# FPGA_ADC3.net
KiCad netlist of a schematic drawn in Altium Designer
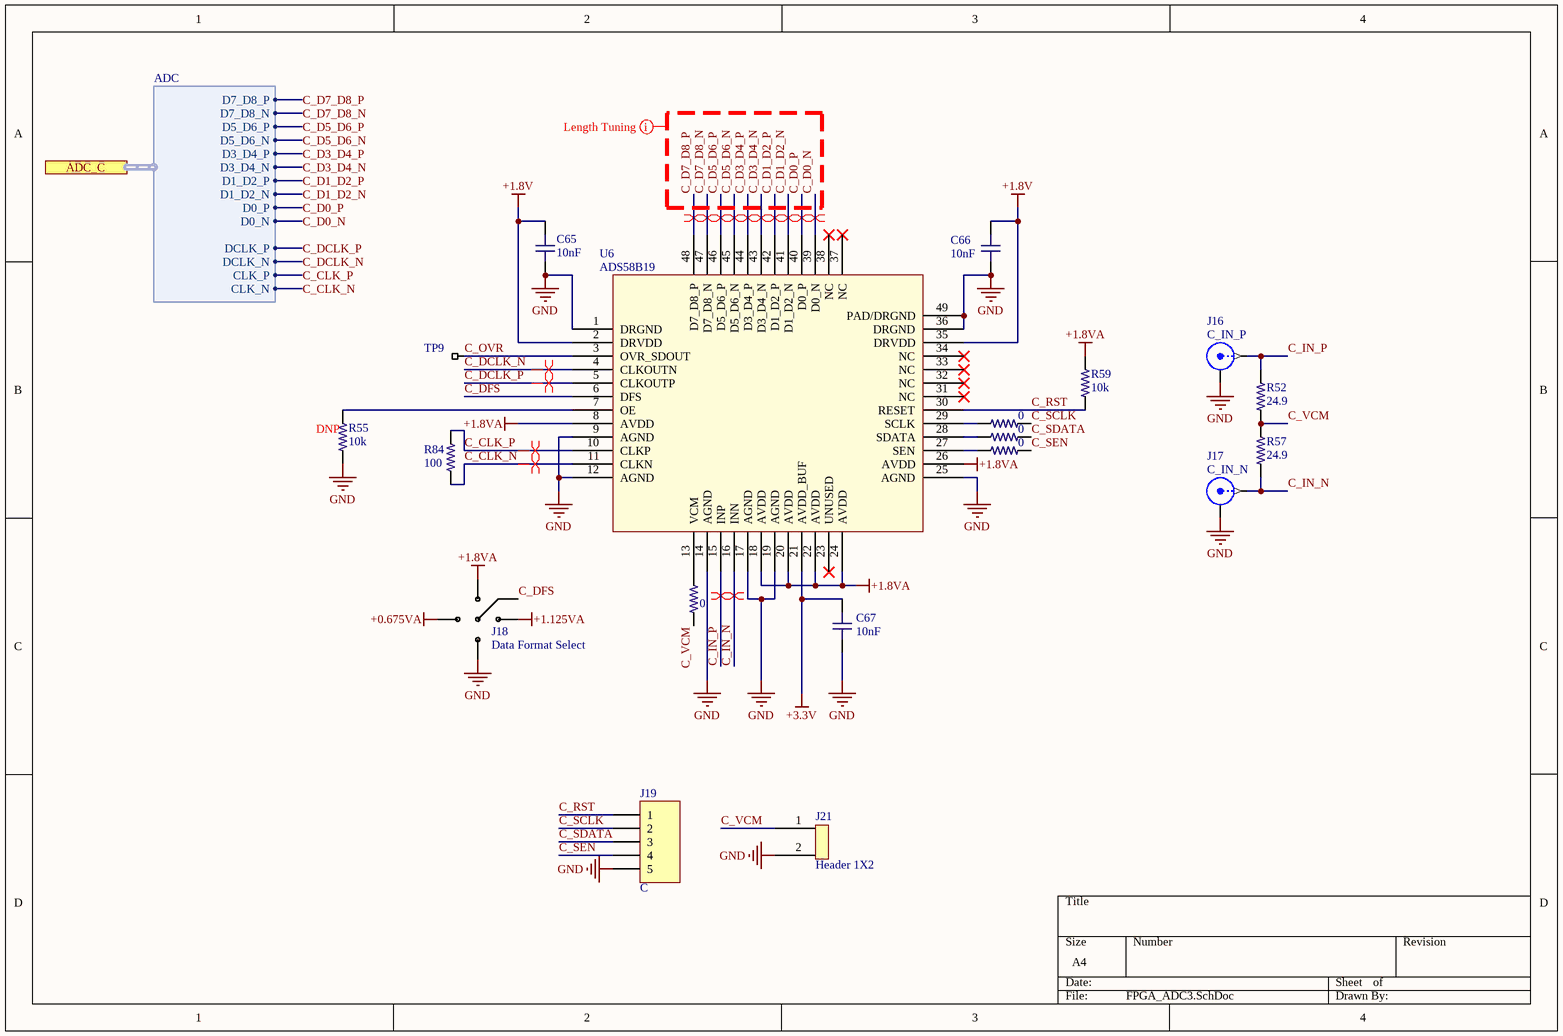
[diagram p0: FPGA_ADC3.SchDoc]

(export (version "E")
  (design (tool "Eeschema 10.0.6"))
  (components
    (comp (ref "C65")
      (value "10nF")
      (footprint "C0603-HIGH-DENSITY")
      (description "CAP CER 10000PF 50V X7R 0603")
      (fields (field (name "Comment") "C0603 10nF 50V X7R"))
      (libsource (lib "Capacitors") (part "C0603 10nF 50V X7R"))
    )
    (comp (ref "C66")
      (value "10nF")
      (footprint "C0603-HIGH-DENSITY")
      (description "CAP CER 10000PF 50V X7R 0603")
      (fields (field (name "Comment") "C0603 10nF 50V X7R"))
      (libsource (lib "Capacitors") (part "C0603 10nF 50V X7R"))
    )
    (comp (ref "C67")
      (value "10nF")
      (footprint "C0603-HIGH-DENSITY")
      (description "CAP CER 10000PF 50V X7R 0603")
      (fields (field (name "Comment") "C0603 10nF 50V X7R"))
      (libsource (lib "Capacitors") (part "C0603 10nF 50V X7R"))
    )
    (comp (ref "J16")
      (value "C_IN_P")
      (footprint "SMA Edge Launch (Horizontal)")
      (description "SMA Connector")
      (libsource (lib "Connectors") (part "SMA"))
    )
    (comp (ref "J17")
      (value "C_IN_N")
      (footprint "SMA Edge Launch (Horizontal)")
      (description "SMA Connector")
      (libsource (lib "Connectors") (part "SMA"))
    )
    (comp (ref "J18")
      (value "Data Format Select")
      (footprint "4P Jumper")
      (description "0603 4 Way Solder Jumper")
      (libsource (lib "Switches") (part "4P Jumper"))
    )
    (comp (ref "J19")
      (value "C")
      (footprint "HDR1X5")
      (description "Header, 5-Pin")
      (fields (field (name "PUBLISHER") "Altium Limited"))
      (libsource (lib "Miscellaneous Connectors") (part "Header 5"))
    )
    (comp (ref "J21")
      (value "Header 1X2")
      (footprint "Header 1x2 TH Pitch 2.54mm")
      (libsource (lib "Connectors") (part "Header 1X2"))
    )
    (comp (ref "R52")
      (value "24.9")
      (footprint "R0603-HIGH-DENSITY")
      (description "Chip Resistor, 0603, 24.9 ohms, 0.1W")
      (fields (field (name "Comment") "RC0603FR-0724R9L"))
      (libsource (lib "Resistors") (part "R0603 24.9R 1%"))
    )
    (comp (ref "R53")
      (value "0")
      (footprint "R0603-IPC")
      (description "RES SMD 0 OHM JUMPER 1/10W 0603")
      (fields (field (name "Comment") "R0603 0"))
      (libsource (lib "Resistors") (part "R0603 0"))
    )
    (comp (ref "R54")
      (value "0")
      (footprint "R0603-IPC")
      (description "RES SMD 0 OHM JUMPER 1/10W 0603")
      (fields (field (name "Comment") "R0603 0"))
      (libsource (lib "Resistors") (part "R0603 0"))
    )
    (comp (ref "R55")
      (value "10k")
      (footprint "R0603-IPC-10K")
      (description "RES SMD 10K OHM 1% 1/10W 0603")
      (fields (field (name "Comment") "R0603 10K 1%"))
      (libsource (lib "Resistors") (part "R0603 10K 1%"))
    )
    (comp (ref "R56")
      (value "0")
      (footprint "R0603-IPC")
      (description "RES SMD 0 OHM JUMPER 1/10W 0603")
      (fields (field (name "Comment") "R0603 0"))
      (libsource (lib "Resistors") (part "R0603 0"))
    )
    (comp (ref "R57")
      (value "24.9")
      (footprint "R0603-HIGH-DENSITY")
      (description "Chip Resistor, 0603, 24.9 ohms, 0.1W")
      (fields (field (name "Comment") "RC0603FR-0724R9L"))
      (libsource (lib "Resistors") (part "R0603 24.9R 1%"))
    )
    (comp (ref "R58")
      (value "0")
      (footprint "R0603-IPC")
      (description "RES SMD 0 OHM JUMPER 1/10W 0603")
      (fields (field (name "Comment") "R0603 0"))
      (libsource (lib "Resistors") (part "R0603 0"))
    )
    (comp (ref "R59")
      (value "10k")
      (footprint "R0603-IPC-10K")
      (description "RES SMD 10K OHM 1% 1/10W 0603")
      (fields (field (name "Comment") "R0603 10K 1%"))
      (libsource (lib "Resistors") (part "R0603 10K 1%"))
    )
    (comp (ref "R84")
      (value "100")
      (footprint "R0402-HIGH-DENSITY")
      (description "Chip Resistor, 0402, 100 ohms, 1%, 1/16 W")
      (fields (field (name "Comment") "R0402 100R 1%"))
      (libsource (lib "Resistors") (part "R0402 100R 1%"))
    )
    (comp (ref "TP9")
      (value "Testpoint_SMT")
      (footprint "TESTPOINT_SMT")
      (description "SMT Test Point")
      (libsource (lib "Virtual Parts") (part "Testpoint_SMT"))
    )
    (comp (ref "U6")
      (value "ADS58B19")
      (footprint "VQFN48")
      (description "Single ADC Pipelined 250Msps 9-bit Parallel/LVDS 48-Pin VQFN")
      (libsource (lib "Integrated Circuits") (part "ADS58B19"))
    )
  )
  (nets
    (net (code "2") (name "+0.675VA") (class "Default")
      (node (ref "J18") (pin "4") (pinfunction "4_4") (pintype "passive"))
    )
    (net (code "3") (name "+1.8V") (class "Default")
      (node (ref "C65") (pin "1") (pintype "passive"))
      (node (ref "C66") (pin "1") (pintype "passive"))
      (node (ref "U6") (pin "2") (pinfunction "DRVDD_2") (pintype "passive"))
      (node (ref "U6") (pin "35") (pinfunction "DRVDD_35") (pintype "passive"))
    )
    (net (code "4") (name "+1.8VA") (class "Default")
      (node (ref "J18") (pin "1") (pinfunction "1_1") (pintype "passive"))
      (node (ref "R59") (pin "2") (pintype "passive"))
      (node (ref "U6") (pin "18") (pinfunction "AVDD_18") (pintype "passive"))
      (node (ref "U6") (pin "20") (pinfunction "AVDD_20") (pintype "passive"))
      (node (ref "U6") (pin "22") (pinfunction "AVDD_22") (pintype "passive"))
      (node (ref "U6") (pin "24") (pinfunction "AVDD_24") (pintype "passive"))
      (node (ref "U6") (pin "26") (pinfunction "AVDD_26") (pintype "passive"))
      (node (ref "U6") (pin "8") (pinfunction "AVDD_8") (pintype "passive"))
    )
    (net (code "5") (name "+1.125VA") (class "Default")
      (node (ref "J18") (pin "2") (pinfunction "2_2") (pintype "passive"))
    )
    (net (code "6") (name "+3.3V") (class "Default")
      (node (ref "C67") (pin "1") (pintype "passive"))
      (node (ref "U6") (pin "21") (pinfunction "AVDD_BUF_21") (pintype "passive"))
    )
    (net (code "7") (name "/C_CLK_N") (class "Default")
      (node (ref "R84") (pin "1") (pintype "passive"))
      (node (ref "U6") (pin "11") (pinfunction "CLKN_11") (pintype "passive"))
    )
    (net (code "8") (name "/C_CLK_P") (class "Default")
      (node (ref "R84") (pin "2") (pintype "passive"))
      (node (ref "U6") (pin "10") (pinfunction "CLKP_10") (pintype "passive"))
    )
    (net (code "9") (name "/C_D0_N") (class "Default")
      (node (ref "U6") (pin "39") (pinfunction "D0_N_39") (pintype "passive"))
    )
    (net (code "10") (name "/C_D0_P") (class "Default")
      (node (ref "U6") (pin "40") (pinfunction "D0_P_40") (pintype "passive"))
    )
    (net (code "11") (name "/C_D1_D2_N") (class "Default")
      (node (ref "U6") (pin "41") (pinfunction "D1_D2_N_41") (pintype "passive"))
    )
    (net (code "12") (name "/C_D1_D2_P") (class "Default")
      (node (ref "U6") (pin "42") (pinfunction "D1_D2_P_42") (pintype "passive"))
    )
    (net (code "13") (name "/C_D3_D4_N") (class "Default")
      (node (ref "U6") (pin "43") (pinfunction "D3_D4_N_43") (pintype "passive"))
    )
    (net (code "14") (name "/C_D3_D4_P") (class "Default")
      (node (ref "U6") (pin "44") (pinfunction "D3_D4_P_44") (pintype "passive"))
    )
    (net (code "15") (name "/C_D5_D6_N") (class "Default")
      (node (ref "U6") (pin "45") (pinfunction "D5_D6_N_45") (pintype "passive"))
    )
    (net (code "16") (name "/C_D5_D6_P") (class "Default")
      (node (ref "U6") (pin "46") (pinfunction "D5_D6_P_46") (pintype "passive"))
    )
    (net (code "17") (name "/C_D7_D8_N") (class "Default")
      (node (ref "U6") (pin "47") (pinfunction "D7_D8_N_47") (pintype "passive"))
    )
    (net (code "18") (name "/C_D7_D8_P") (class "Default")
      (node (ref "U6") (pin "48") (pinfunction "D7_D8_P_48") (pintype "passive"))
    )
    (net (code "19") (name "/C_DCLK_N") (class "Default")
      (node (ref "U6") (pin "4") (pinfunction "CLKOUTN_4") (pintype "passive"))
    )
    (net (code "20") (name "/C_DCLK_P") (class "Default")
      (node (ref "U6") (pin "5") (pinfunction "CLKOUTP_5") (pintype "passive"))
    )
    (net (code "21") (name "/C_DFS") (class "Default")
      (node (ref "J18") (pin "5") (pinfunction "5_5") (pintype "passive"))
      (node (ref "U6") (pin "6") (pinfunction "DFS_6") (pintype "passive"))
    )
    (net (code "22") (name "/C_IN_N") (class "Default")
      (node (ref "J17") (pin "1") (pinfunction "X_1") (pintype "output"))
      (node (ref "R57") (pin "1") (pintype "passive"))
      (node (ref "U6") (pin "16") (pinfunction "INN_16") (pintype "passive"))
    )
    (net (code "23") (name "/C_IN_P") (class "Default")
      (node (ref "J16") (pin "1") (pinfunction "X_1") (pintype "output"))
      (node (ref "R52") (pin "2") (pintype "passive"))
      (node (ref "U6") (pin "15") (pinfunction "INP_15") (pintype "passive"))
    )
    (net (code "24") (name "/C_OVR") (class "Default")
      (node (ref "TP9") (pin "1") (pinfunction "1_1") (pintype "passive"))
      (node (ref "U6") (pin "3") (pinfunction "OVR_SDOUT_3") (pintype "passive"))
    )
    (net (code "25") (name "/C_RST") (class "Default")
      (node (ref "J19") (pin "1") (pinfunction "1_1") (pintype "passive"))
      (node (ref "R59") (pin "1") (pintype "passive"))
      (node (ref "U6") (pin "30") (pinfunction "RESET_30") (pintype "passive"))
    )
    (net (code "26") (name "/C_SCLK") (class "Default")
      (node (ref "J19") (pin "2") (pinfunction "2_2") (pintype "passive"))
      (node (ref "R53") (pin "2") (pintype "passive"))
    )
    (net (code "27") (name "/C_SDATA") (class "Default")
      (node (ref "J19") (pin "3") (pinfunction "3_3") (pintype "passive"))
      (node (ref "R54") (pin "2") (pintype "passive"))
    )
    (net (code "28") (name "/C_SEN") (class "Default")
      (node (ref "J19") (pin "4") (pinfunction "4_4") (pintype "passive"))
      (node (ref "R56") (pin "2") (pintype "passive"))
    )
    (net (code "29") (name "/C_VCM") (class "Default")
      (node (ref "J21") (pin "1") (pintype "passive"))
      (node (ref "R52") (pin "1") (pintype "passive"))
      (node (ref "R57") (pin "2") (pintype "passive"))
      (node (ref "R58") (pin "2") (pintype "passive"))
    )
    (net (code "31") (name "GND") (class "Default")
      (node (ref "C65") (pin "2") (pintype "passive"))
      (node (ref "C66") (pin "2") (pintype "passive"))
      (node (ref "C67") (pin "2") (pintype "passive"))
      (node (ref "J16") (pin "2") (pinfunction "Y_2") (pintype "power_in"))
      (node (ref "J17") (pin "2") (pinfunction "Y_2") (pintype "power_in"))
      (node (ref "J18") (pin "3") (pinfunction "3_3") (pintype "passive"))
      (node (ref "J19") (pin "5") (pinfunction "5_5") (pintype "passive"))
      (node (ref "J21") (pin "2") (pintype "passive"))
      (node (ref "R55") (pin "1") (pintype "passive"))
      (node (ref "U6") (pin "1") (pinfunction "DRGND_1") (pintype "passive"))
      (node (ref "U6") (pin "12") (pinfunction "AGND_12") (pintype "passive"))
      (node (ref "U6") (pin "14") (pinfunction "AGND_14") (pintype "passive"))
      (node (ref "U6") (pin "17") (pinfunction "AGND_17") (pintype "passive"))
      (node (ref "U6") (pin "19") (pinfunction "AGND_19") (pintype "passive"))
      (node (ref "U6") (pin "25") (pinfunction "AGND_25") (pintype "passive"))
      (node (ref "U6") (pin "36") (pinfunction "DRGND_36") (pintype "passive"))
      (node (ref "U6") (pin "49") (pinfunction "PAD/DRGND_49") (pintype "passive"))
      (node (ref "U6") (pin "9") (pinfunction "AGND_9") (pintype "passive"))
    )
    (net (code "32") (name "Net-(U6-OE)") (class "Default")
      (node (ref "R55") (pin "2") (pintype "passive"))
      (node (ref "U6") (pin "7") (pinfunction "OE_7") (pintype "passive"))
    )
    (net (code "33") (name "Net-(U6-SCLK)") (class "Default")
      (node (ref "R53") (pin "1") (pintype "passive"))
      (node (ref "U6") (pin "29") (pinfunction "SCLK_29") (pintype "passive"))
    )
    (net (code "34") (name "Net-(U6-SDATA)") (class "Default")
      (node (ref "R54") (pin "1") (pintype "passive"))
      (node (ref "U6") (pin "28") (pinfunction "SDATA_28") (pintype "passive"))
    )
    (net (code "35") (name "Net-(U6-SEN)") (class "Default")
      (node (ref "R56") (pin "1") (pintype "passive"))
      (node (ref "U6") (pin "27") (pinfunction "SEN_27") (pintype "passive"))
    )
    (net (code "36") (name "Net-(U6-VCM)") (class "Default")
      (node (ref "R58") (pin "1") (pintype "passive"))
      (node (ref "U6") (pin "13") (pinfunction "VCM_13") (pintype "passive"))
    )
    (net (code "37") (name "unconnected-(U6-NC-Pad31)") (class "Default")
      (node (ref "U6") (pin "31") (pinfunction "NC_31") (pintype "passive+no_connect"))
    )
    (net (code "38") (name "unconnected-(U6-NC-Pad32)") (class "Default")
      (node (ref "U6") (pin "32") (pinfunction "NC_32") (pintype "passive+no_connect"))
    )
    (net (code "39") (name "unconnected-(U6-NC-Pad33)") (class "Default")
      (node (ref "U6") (pin "33") (pinfunction "NC_33") (pintype "passive+no_connect"))
    )
    (net (code "40") (name "unconnected-(U6-NC-Pad34)") (class "Default")
      (node (ref "U6") (pin "34") (pinfunction "NC_34") (pintype "passive+no_connect"))
    )
    (net (code "41") (name "unconnected-(U6-NC-Pad37)") (class "Default")
      (node (ref "U6") (pin "37") (pinfunction "NC_37") (pintype "passive+no_connect"))
    )
    (net (code "42") (name "unconnected-(U6-NC-Pad38)") (class "Default")
      (node (ref "U6") (pin "38") (pinfunction "NC_38") (pintype "passive+no_connect"))
    )
    (net (code "43") (name "unconnected-(U6-UNUSED-Pad23)") (class "Default")
      (node (ref "U6") (pin "23") (pinfunction "UNUSED_23") (pintype "passive+no_connect"))
    )
  )
)
